# STM32.net
KiCad netlist of a schematic drawn in Altium Designer
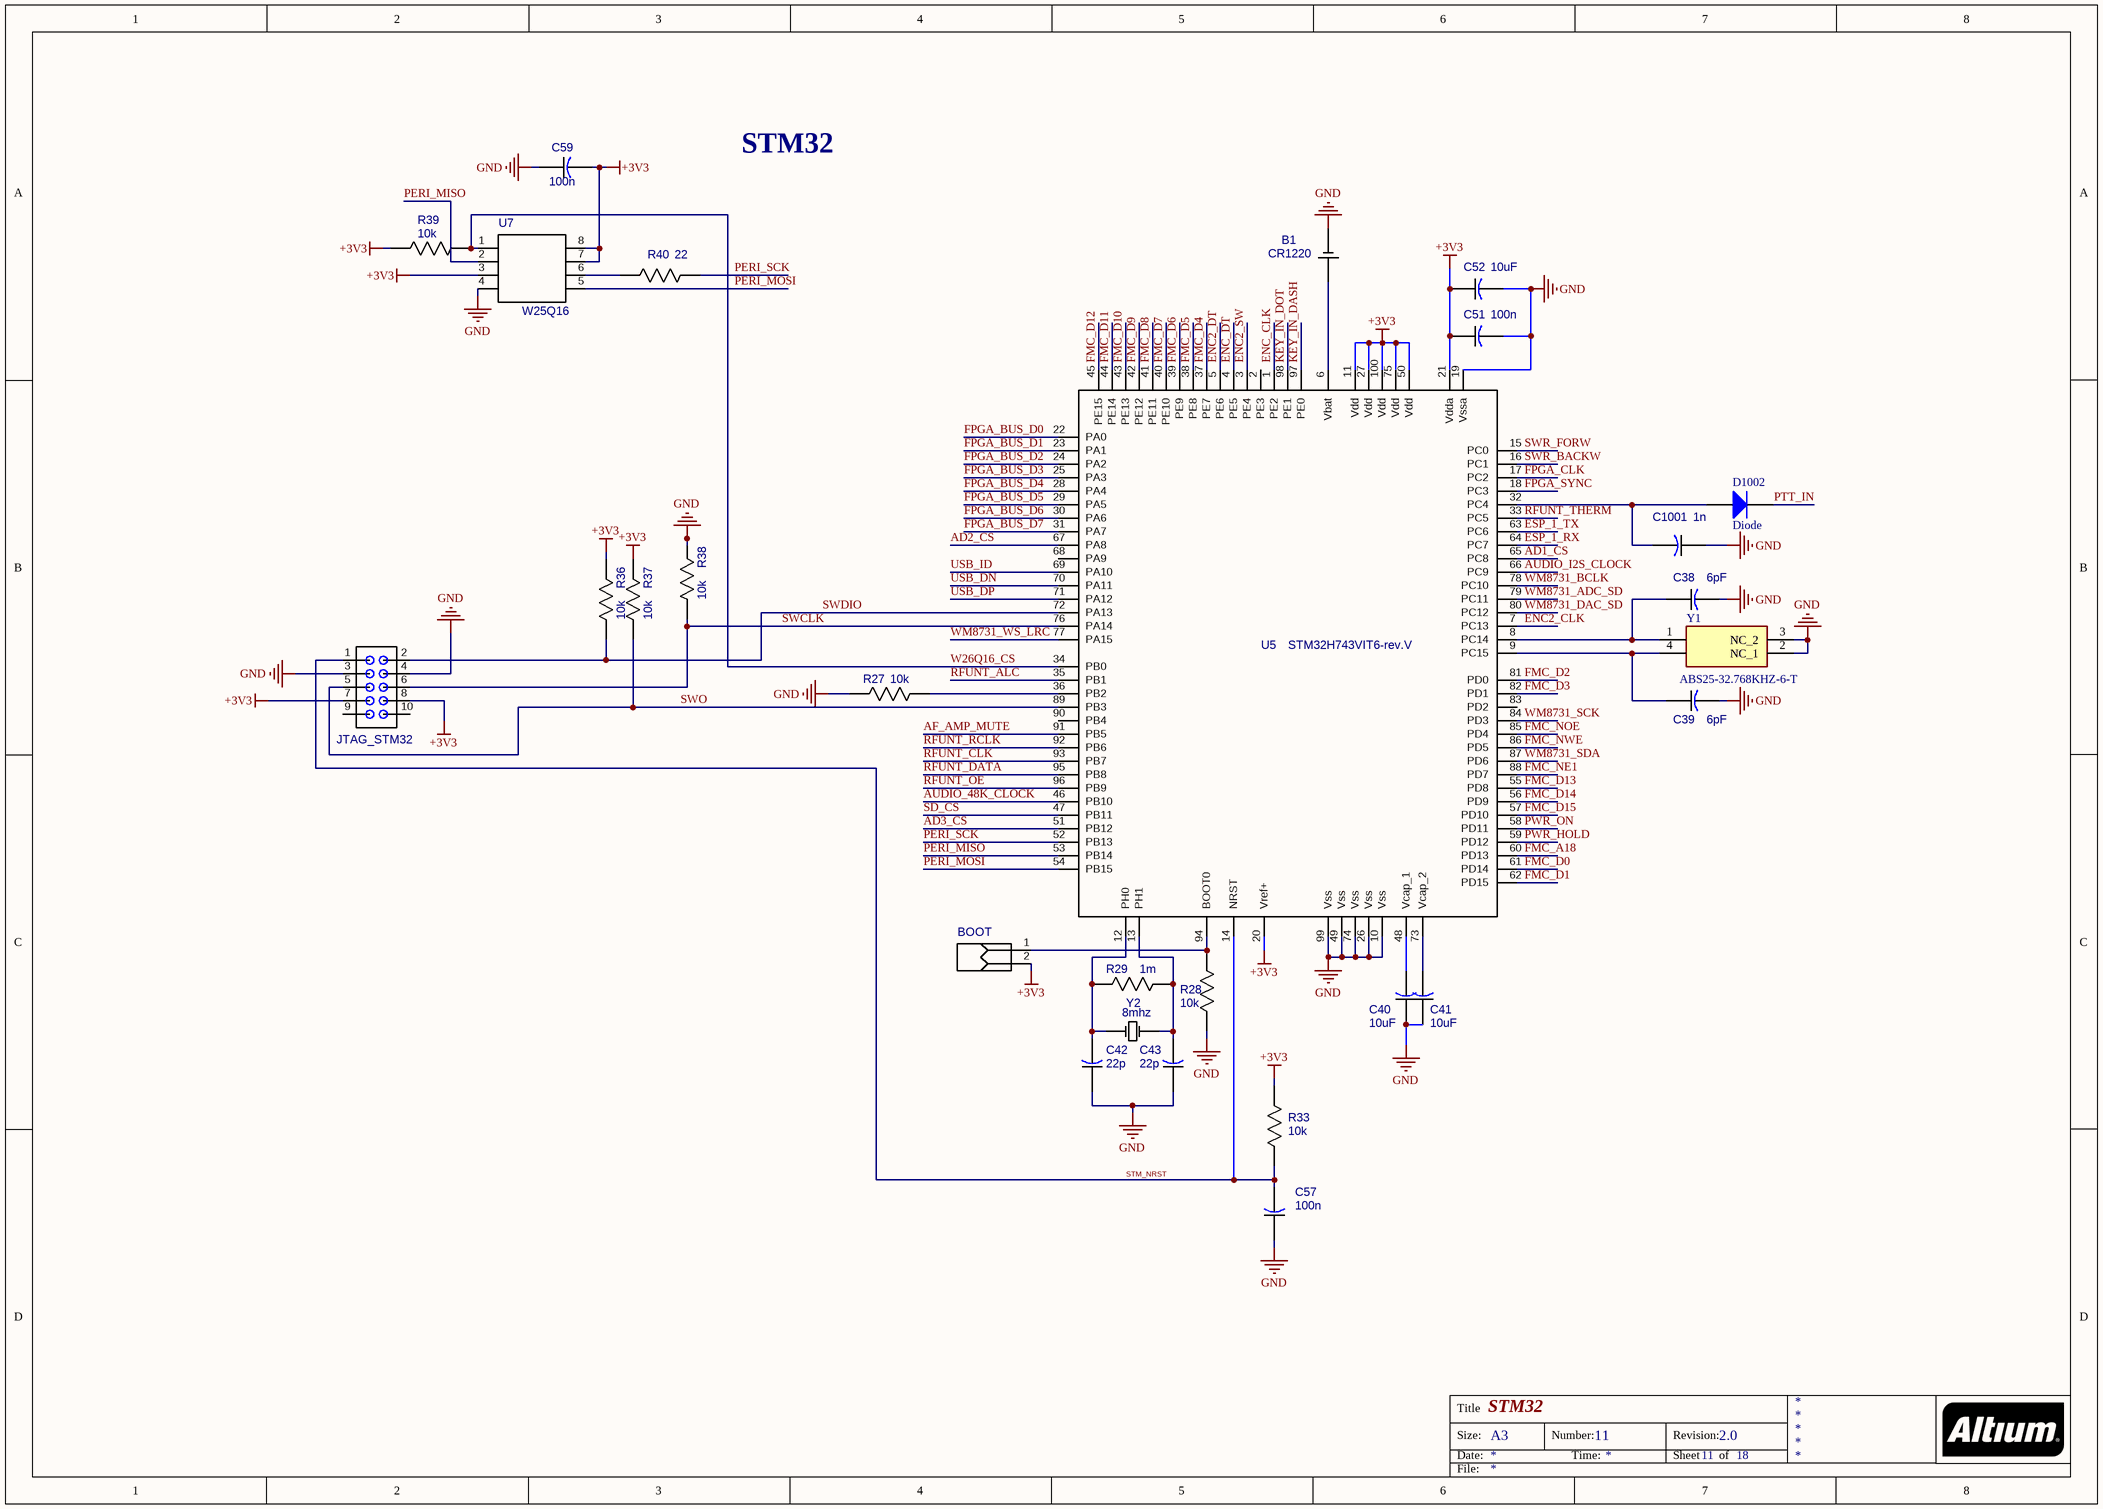
[diagram p0: STM32.SchDoc]

(export (version "E")
  (design (tool "Eeschema 10.0.6"))
  (components
    (comp (ref "B1")
      (value "CR1220")
      (footprint "KLS5-CR1220-01")
      (description "BR1632A/FA")
      (fields (field (name "Comment") "CR1220 +"))
      (libsource (lib "*") (part "BR1632A/FA"))
    )
    (comp (ref "BOOT")
      (value "~")
      (footprint "51022-0200")
      (description "2 Pin")
      (libsource (lib "*") (part "51022-0200"))
    )
    (comp (ref "C38")
      (value "6pF")
      (footprint "CAP_0805")
      (description "CAP_0805")
      (libsource (lib "*") (part "CAP_0805"))
    )
    (comp (ref "C39")
      (value "6pF")
      (footprint "CAP_0805")
      (description "CAP_0805")
      (libsource (lib "*") (part "CAP_0805"))
    )
    (comp (ref "C40")
      (value "10uF")
      (footprint "CAP_0805")
      (description "CAP_0805")
      (libsource (lib "*") (part "CAP_0805"))
    )
    (comp (ref "C41")
      (value "10uF")
      (footprint "CAP_0805")
      (description "CAP_0805")
      (libsource (lib "*") (part "CAP_0805"))
    )
    (comp (ref "C42")
      (value "22p")
      (footprint "CAP_0805")
      (description "CAP_0805")
      (libsource (lib "*") (part "CAP_0805"))
    )
    (comp (ref "C43")
      (value "22p")
      (footprint "CAP_0805")
      (description "CAP_0805")
      (libsource (lib "*") (part "CAP_0805"))
    )
    (comp (ref "C51")
      (value "100n")
      (footprint "CAP_0805")
      (description "CAP_0805")
      (libsource (lib "*") (part "CAP_0805"))
    )
    (comp (ref "C52")
      (value "10uF")
      (footprint "CAP_0805")
      (description "CAP_0805")
      (libsource (lib "*") (part "CAP_0805"))
    )
    (comp (ref "C57")
      (value "100n")
      (footprint "CAP_0805")
      (description "CAP_0805")
      (libsource (lib "*") (part "CAP_0805"))
    )
    (comp (ref "C59")
      (value "100n")
      (footprint "CAP_0805")
      (description "CAP_0805")
      (libsource (lib "*") (part "CAP_0805"))
    )
    (comp (ref "C1001")
      (value "1n")
      (footprint "CAP_0805")
      (description "CAP_0805")
      (libsource (lib "*") (part "CAP_0805"))
    )
    (comp (ref "D1002")
      (value "Diode")
      (footprint "C1206")
      (description "Default Diode")
      (fields (field (name "PUBLISHER") "Altium Limited"))
      (libsource (lib "Miscellaneous Devices") (part "Diode"))
    )
    (comp (ref "JTAG_STM32")
      (value "~")
      (footprint "IDC10")
      (description "2*5 Pin")
      (libsource (lib "*") (part "IDC10"))
    )
    (comp (ref "R27")
      (value "10k")
      (footprint "RES_0805")
      (description "RES_0805")
      (libsource (lib "*") (part "RES_0805"))
    )
    (comp (ref "R28")
      (value "10k")
      (footprint "RES_0805")
      (description "RES_0805")
      (libsource (lib "*") (part "RES_0805"))
    )
    (comp (ref "R29")
      (value "1m")
      (footprint "RES_0805")
      (description "RES_0805")
      (libsource (lib "*") (part "RES_0805"))
    )
    (comp (ref "R33")
      (value "10k")
      (footprint "RES_0805")
      (description "RES_0805")
      (libsource (lib "*") (part "RES_0805"))
    )
    (comp (ref "R36")
      (value "10k")
      (footprint "RES_0805")
      (description "RES_0805")
      (libsource (lib "*") (part "RES_0805"))
    )
    (comp (ref "R37")
      (value "10k")
      (footprint "RES_0805")
      (description "RES_0805")
      (libsource (lib "*") (part "RES_0805"))
    )
    (comp (ref "R38")
      (value "10k")
      (footprint "RES_0805")
      (description "RES_0805")
      (libsource (lib "*") (part "RES_0805"))
    )
    (comp (ref "R39")
      (value "10k")
      (footprint "RES_0805")
      (description "RES_0805")
      (libsource (lib "*") (part "RES_0805"))
    )
    (comp (ref "R40")
      (value "22")
      (footprint "RES_0805")
      (description "RES_0805")
      (libsource (lib "*") (part "RES_0805"))
    )
    (comp (ref "U5")
      (value "STM32H743VIT6-rev.V")
      (footprint "STM32H743VIT6")
      (description "STM32H743VIT6")
      (libsource (lib "*") (part "STM32H743VIT6"))
    )
    (comp (ref "U7") (value "W25Q16") (footprint "W25Q16") (libsource (lib "*") (part "W25Q16")))
    (comp (ref "Y1")
      (value "ABS25-32.768KHZ-6-T")
      (footprint "SamacSys:ABS25")
      (description "Crystal or Oscillator")
      (fields
        (field (name "MOUSER PART NUMBER") "815-ABS25-32.768K6-T")
        (field (name "RS PART NUMBER") "1712795P")
      )
      (libsource (lib "*") (part "ABS25-32.768KHZ-6-T"))
    )
    (comp (ref "Y2")
      (value "8mhz")
      (footprint "ECS-200-20-1")
      (description "ECS-200-20-1")
      (libsource (lib "*") (part "ECS-200-20-1"))
    )
  )
  (nets
    (net (code "1") (name "+3V3") (class "Default")
      (node (ref "BOOT") (pin "2") (pinfunction "2_2") (pintype "passive"))
      (node (ref "C51") (pin "1") (pinfunction "1_1") (pintype "passive"))
      (node (ref "C52") (pin "1") (pinfunction "1_1") (pintype "passive"))
      (node (ref "C59") (pin "2") (pinfunction "2_2") (pintype "passive"))
      (node (ref "JTAG_STM32") (pin "7") (pinfunction "7_7") (pintype "passive"))
      (node (ref "JTAG_STM32") (pin "8") (pinfunction "8_8") (pintype "passive"))
      (node (ref "R33") (pin "2") (pinfunction "2_2") (pintype "passive"))
      (node (ref "R36") (pin "1") (pinfunction "1_1") (pintype "passive"))
      (node (ref "R37") (pin "1") (pinfunction "1_1") (pintype "passive"))
      (node (ref "R39") (pin "1") (pinfunction "1_1") (pintype "passive"))
      (node (ref "U5") (pin "100") (pinfunction "Vdd_100") (pintype "passive"))
      (node (ref "U5") (pin "11") (pinfunction "Vdd_11") (pintype "passive"))
      (node (ref "U5") (pin "20") (pinfunction "Vref+_20") (pintype "passive"))
      (node (ref "U5") (pin "21") (pinfunction "Vdda_21") (pintype "passive"))
      (node (ref "U5") (pin "27") (pinfunction "Vdd_27") (pintype "passive"))
      (node (ref "U5") (pin "50") (pinfunction "Vdd_50") (pintype "passive"))
      (node (ref "U5") (pin "75") (pinfunction "Vdd_75") (pintype "passive"))
      (node (ref "U7") (pin "3") (pinfunction "WP_3") (pintype "passive"))
      (node (ref "U7") (pin "7") (pinfunction "HOLD_7") (pintype "passive"))
      (node (ref "U7") (pin "8") (pinfunction "VCC_8") (pintype "passive"))
    )
    (net (code "2") (name "/AD1_CS") (class "Default")
      (node (ref "U5") (pin "65") (pinfunction "PC8_65") (pintype "passive"))
    )
    (net (code "3") (name "/AD2_CS") (class "Default")
      (node (ref "U5") (pin "67") (pinfunction "PA8_67") (pintype "passive"))
    )
    (net (code "4") (name "/AD3_CS") (class "Default")
      (node (ref "U5") (pin "51") (pinfunction "PB12_51") (pintype "passive"))
    )
    (net (code "5") (name "/AF_AMP_MUTE") (class "Default")
      (node (ref "U5") (pin "91") (pinfunction "PB5_91") (pintype "passive"))
    )
    (net (code "6") (name "/AUDIO_48K_CLOCK") (class "Default")
      (node (ref "U5") (pin "46") (pinfunction "PB10_46") (pintype "passive"))
    )
    (net (code "7") (name "/AUDIO_I2S_CLOCK") (class "Default")
      (node (ref "U5") (pin "66") (pinfunction "PC9_66") (pintype "passive"))
    )
    (net (code "8") (name "/ENC2_CLK") (class "Default")
      (node (ref "U5") (pin "7") (pinfunction "PC13_7") (pintype "passive"))
    )
    (net (code "9") (name "/ENC2_DT") (class "Default")
      (node (ref "U5") (pin "5") (pinfunction "PE6_5") (pintype "passive"))
    )
    (net (code "10") (name "/ENC2_SW") (class "Default")
      (node (ref "U5") (pin "3") (pinfunction "PE4_3") (pintype "passive"))
    )
    (net (code "11") (name "/ENC_CLK") (class "Default")
      (node (ref "U5") (pin "1") (pinfunction "PE2_1") (pintype "passive"))
    )
    (net (code "12") (name "/ENC_DT") (class "Default")
      (node (ref "U5") (pin "4") (pinfunction "PE5_4") (pintype "passive"))
    )
    (net (code "13") (name "/ESP_1_RX") (class "Default")
      (node (ref "U5") (pin "64") (pinfunction "PC7_64") (pintype "passive"))
    )
    (net (code "14") (name "/ESP_1_TX") (class "Default")
      (node (ref "U5") (pin "63") (pinfunction "PC6_63") (pintype "passive"))
    )
    (net (code "15") (name "/FMC_A18") (class "Default")
      (node (ref "U5") (pin "60") (pinfunction "PD13_60") (pintype "passive"))
    )
    (net (code "16") (name "/FMC_D0") (class "Default")
      (node (ref "U5") (pin "61") (pinfunction "PD14_61") (pintype "passive"))
    )
    (net (code "17") (name "/FMC_D1") (class "Default")
      (node (ref "U5") (pin "62") (pinfunction "PD15_62") (pintype "passive"))
    )
    (net (code "18") (name "/FMC_D2") (class "Default")
      (node (ref "U5") (pin "81") (pinfunction "PD0_81") (pintype "passive"))
    )
    (net (code "19") (name "/FMC_D3") (class "Default")
      (node (ref "U5") (pin "82") (pinfunction "PD1_82") (pintype "passive"))
    )
    (net (code "20") (name "/FMC_D4") (class "Default")
      (node (ref "U5") (pin "37") (pinfunction "PE7_37") (pintype "passive"))
    )
    (net (code "21") (name "/FMC_D5") (class "Default")
      (node (ref "U5") (pin "38") (pinfunction "PE8_38") (pintype "passive"))
    )
    (net (code "22") (name "/FMC_D6") (class "Default")
      (node (ref "U5") (pin "39") (pinfunction "PE9_39") (pintype "passive"))
    )
    (net (code "23") (name "/FMC_D7") (class "Default")
      (node (ref "U5") (pin "40") (pinfunction "PE10_40") (pintype "passive"))
    )
    (net (code "24") (name "/FMC_D8") (class "Default")
      (node (ref "U5") (pin "41") (pinfunction "PE11_41") (pintype "passive"))
    )
    (net (code "25") (name "/FMC_D9") (class "Default")
      (node (ref "U5") (pin "42") (pinfunction "PE12_42") (pintype "passive"))
    )
    (net (code "26") (name "/FMC_D10") (class "Default")
      (node (ref "U5") (pin "43") (pinfunction "PE13_43") (pintype "passive"))
    )
    (net (code "27") (name "/FMC_D11") (class "Default")
      (node (ref "U5") (pin "44") (pinfunction "PE14_44") (pintype "passive"))
    )
    (net (code "28") (name "/FMC_D12") (class "Default")
      (node (ref "U5") (pin "45") (pinfunction "PE15_45") (pintype "passive"))
    )
    (net (code "29") (name "/FMC_D13") (class "Default")
      (node (ref "U5") (pin "55") (pinfunction "PD8_55") (pintype "passive"))
    )
    (net (code "30") (name "/FMC_D14") (class "Default")
      (node (ref "U5") (pin "56") (pinfunction "PD9_56") (pintype "passive"))
    )
    (net (code "31") (name "/FMC_D15") (class "Default")
      (node (ref "U5") (pin "57") (pinfunction "PD10_57") (pintype "passive"))
    )
    (net (code "32") (name "/FMC_NE1") (class "Default")
      (node (ref "U5") (pin "88") (pinfunction "PD7_88") (pintype "passive"))
    )
    (net (code "33") (name "/FMC_NOE") (class "Default")
      (node (ref "U5") (pin "85") (pinfunction "PD4_85") (pintype "passive"))
    )
    (net (code "34") (name "/FMC_NWE") (class "Default")
      (node (ref "U5") (pin "86") (pinfunction "PD5_86") (pintype "passive"))
    )
    (net (code "35") (name "/FPGA_BUS_D0") (class "Default")
      (node (ref "U5") (pin "22") (pinfunction "PA0_22") (pintype "passive"))
    )
    (net (code "36") (name "/FPGA_BUS_D1") (class "Default")
      (node (ref "U5") (pin "23") (pinfunction "PA1_23") (pintype "passive"))
    )
    (net (code "37") (name "/FPGA_BUS_D2") (class "Default")
      (node (ref "U5") (pin "24") (pinfunction "PA2_24") (pintype "passive"))
    )
    (net (code "38") (name "/FPGA_BUS_D3") (class "Default")
      (node (ref "U5") (pin "25") (pinfunction "PA3_25") (pintype "passive"))
    )
    (net (code "39") (name "/FPGA_BUS_D4") (class "Default")
      (node (ref "U5") (pin "28") (pinfunction "PA4_28") (pintype "passive"))
    )
    (net (code "40") (name "/FPGA_BUS_D5") (class "Default")
      (node (ref "U5") (pin "29") (pinfunction "PA5_29") (pintype "passive"))
    )
    (net (code "41") (name "/FPGA_BUS_D6") (class "Default")
      (node (ref "U5") (pin "30") (pinfunction "PA6_30") (pintype "passive"))
    )
    (net (code "42") (name "/FPGA_BUS_D7") (class "Default")
      (node (ref "U5") (pin "31") (pinfunction "PA7_31") (pintype "passive"))
    )
    (net (code "43") (name "/FPGA_CLK") (class "Default")
      (node (ref "U5") (pin "17") (pinfunction "PC2_17") (pintype "passive"))
    )
    (net (code "44") (name "/FPGA_SYNC") (class "Default")
      (node (ref "U5") (pin "18") (pinfunction "PC3_18") (pintype "passive"))
    )
    (net (code "45") (name "/KEY_IN_DASH") (class "Default")
      (node (ref "U5") (pin "97") (pinfunction "PE0_97") (pintype "passive"))
    )
    (net (code "46") (name "/KEY_IN_DOT") (class "Default")
      (node (ref "U5") (pin "98") (pinfunction "PE1_98") (pintype "passive"))
    )
    (net (code "47") (name "/PERI_MISO") (class "Default")
      (node (ref "U5") (pin "53") (pinfunction "PB14_53") (pintype "passive"))
      (node (ref "U7") (pin "2") (pinfunction "SO_2") (pintype "passive"))
    )
    (net (code "48") (name "/PERI_MOSI") (class "Default")
      (node (ref "U5") (pin "54") (pinfunction "PB15_54") (pintype "passive"))
      (node (ref "U7") (pin "5") (pinfunction "SI_5") (pintype "passive"))
    )
    (net (code "49") (name "/PERI_SCK") (class "Default")
      (node (ref "R40") (pin "2") (pinfunction "2_2") (pintype "passive"))
      (node (ref "U5") (pin "52") (pinfunction "PB13_52") (pintype "passive"))
    )
    (net (code "50") (name "/PTT_IN") (class "Default")
      (node (ref "D1002") (pin "2") (pinfunction "K_2") (pintype "passive"))
    )
    (net (code "51") (name "/PWR_HOLD") (class "Default")
      (node (ref "U5") (pin "59") (pinfunction "PD12_59") (pintype "passive"))
    )
    (net (code "52") (name "/PWR_ON") (class "Default")
      (node (ref "U5") (pin "58") (pinfunction "PD11_58") (pintype "passive"))
    )
    (net (code "53") (name "/RFUNT_ALC") (class "Default")
      (node (ref "U5") (pin "35") (pinfunction "PB1_35") (pintype "passive"))
    )
    (net (code "54") (name "/RFUNT_CLK") (class "Default")
      (node (ref "U5") (pin "93") (pinfunction "PB7_93") (pintype "passive"))
    )
    (net (code "55") (name "/RFUNT_DATA") (class "Default")
      (node (ref "U5") (pin "95") (pinfunction "PB8_95") (pintype "passive"))
    )
    (net (code "56") (name "/RFUNT_OE") (class "Default")
      (node (ref "U5") (pin "96") (pinfunction "PB9_96") (pintype "passive"))
    )
    (net (code "57") (name "/RFUNT_RCLK") (class "Default")
      (node (ref "U5") (pin "92") (pinfunction "PB6_92") (pintype "passive"))
    )
    (net (code "58") (name "/RFUNT_THERM") (class "Default")
      (node (ref "U5") (pin "33") (pinfunction "PC5_33") (pintype "passive"))
    )
    (net (code "59") (name "/SD_CS") (class "Default")
      (node (ref "U5") (pin "47") (pinfunction "PB11_47") (pintype "passive"))
    )
    (net (code "60") (name "/STM_NRST") (class "Default")
      (node (ref "C57") (pin "2") (pinfunction "2_2") (pintype "passive"))
      (node (ref "JTAG_STM32") (pin "1") (pinfunction "1_1") (pintype "passive"))
      (node (ref "R33") (pin "1") (pinfunction "1_1") (pintype "passive"))
      (node (ref "U5") (pin "14") (pinfunction "NRST_14") (pintype "passive"))
    )
    (net (code "61") (name "/SWCLK") (class "Default")
      (node (ref "JTAG_STM32") (pin "6") (pinfunction "6_6") (pintype "passive"))
      (node (ref "R38") (pin "2") (pinfunction "2_2") (pintype "passive"))
      (node (ref "U5") (pin "76") (pinfunction "PA14_76") (pintype "passive"))
    )
    (net (code "62") (name "/SWDIO") (class "Default")
      (node (ref "JTAG_STM32") (pin "2") (pinfunction "2_2") (pintype "passive"))
      (node (ref "R36") (pin "2") (pinfunction "2_2") (pintype "passive"))
      (node (ref "U5") (pin "72") (pinfunction "PA13_72") (pintype "passive"))
    )
    (net (code "63") (name "/SWO") (class "Default")
      (node (ref "JTAG_STM32") (pin "5") (pinfunction "5_5") (pintype "passive"))
      (node (ref "R37") (pin "2") (pinfunction "2_2") (pintype "passive"))
      (node (ref "U5") (pin "89") (pinfunction "PB3_89") (pintype "passive"))
    )
    (net (code "64") (name "/SWR_BACKW") (class "Default")
      (node (ref "U5") (pin "16") (pinfunction "PC1_16") (pintype "passive"))
    )
    (net (code "65") (name "/SWR_FORW") (class "Default")
      (node (ref "U5") (pin "15") (pinfunction "PC0_15") (pintype "passive"))
    )
    (net (code "66") (name "/USB_DN") (class "Default")
      (node (ref "U5") (pin "70") (pinfunction "PA11_70") (pintype "passive"))
    )
    (net (code "67") (name "/USB_DP") (class "Default")
      (node (ref "U5") (pin "71") (pinfunction "PA12_71") (pintype "passive"))
    )
    (net (code "68") (name "/USB_ID") (class "Default")
      (node (ref "U5") (pin "69") (pinfunction "PA10_69") (pintype "passive"))
    )
    (net (code "69") (name "/W26Q16_CS") (class "Default")
      (node (ref "R39") (pin "2") (pinfunction "2_2") (pintype "passive"))
      (node (ref "U5") (pin "34") (pinfunction "PB0_34") (pintype "passive"))
      (node (ref "U7") (pin "1") (pinfunction "CS_1") (pintype "passive"))
    )
    (net (code "70") (name "/WM8731_ADC_SD") (class "Default")
      (node (ref "U5") (pin "79") (pinfunction "PC11_79") (pintype "passive"))
    )
    (net (code "71") (name "/WM8731_BCLK") (class "Default")
      (node (ref "U5") (pin "78") (pinfunction "PC10_78") (pintype "passive"))
    )
    (net (code "72") (name "/WM8731_DAC_SD") (class "Default")
      (node (ref "U5") (pin "80") (pinfunction "PC12_80") (pintype "passive"))
    )
    (net (code "73") (name "/WM8731_SCK") (class "Default")
      (node (ref "U5") (pin "84") (pinfunction "PD3_84") (pintype "passive"))
    )
    (net (code "74") (name "/WM8731_SDA") (class "Default")
      (node (ref "U5") (pin "87") (pinfunction "PD6_87") (pintype "passive"))
    )
    (net (code "75") (name "/WM8731_WS_LRC") (class "Default")
      (node (ref "U5") (pin "77") (pinfunction "PA15_77") (pintype "passive"))
    )
    (net (code "76") (name "GND") (class "Default")
      (node (ref "B1") (pin "2") (pinfunction "NEG_2") (pintype "passive"))
      (node (ref "C1001") (pin "1") (pinfunction "1_1") (pintype "passive"))
      (node (ref "C38") (pin "2") (pinfunction "2_2") (pintype "passive"))
      (node (ref "C39") (pin "2") (pinfunction "2_2") (pintype "passive"))
      (node (ref "C40") (pin "1") (pinfunction "1_1") (pintype "passive"))
      (node (ref "C41") (pin "1") (pinfunction "1_1") (pintype "passive"))
      (node (ref "C42") (pin "1") (pinfunction "1_1") (pintype "passive"))
      (node (ref "C43") (pin "1") (pinfunction "1_1") (pintype "passive"))
      (node (ref "C51") (pin "2") (pinfunction "2_2") (pintype "passive"))
      (node (ref "C52") (pin "2") (pinfunction "2_2") (pintype "passive"))
      (node (ref "C57") (pin "1") (pinfunction "1_1") (pintype "passive"))
      (node (ref "C59") (pin "1") (pinfunction "1_1") (pintype "passive"))
      (node (ref "JTAG_STM32") (pin "3") (pinfunction "3_3") (pintype "passive"))
      (node (ref "JTAG_STM32") (pin "4") (pinfunction "4_4") (pintype "passive"))
      (node (ref "R27") (pin "1") (pinfunction "1_1") (pintype "passive"))
      (node (ref "R28") (pin "1") (pinfunction "1_1") (pintype "passive"))
      (node (ref "R38") (pin "1") (pinfunction "1_1") (pintype "passive"))
      (node (ref "U5") (pin "10") (pinfunction "Vss_10") (pintype "passive"))
      (node (ref "U5") (pin "19") (pinfunction "Vssa_19") (pintype "passive"))
      (node (ref "U5") (pin "26") (pinfunction "Vss_26") (pintype "passive"))
      (node (ref "U5") (pin "49") (pinfunction "Vss_49") (pintype "passive"))
      (node (ref "U5") (pin "74") (pinfunction "Vss_74") (pintype "passive"))
      (node (ref "U5") (pin "99") (pinfunction "Vss_99") (pintype "passive"))
      (node (ref "U7") (pin "4") (pinfunction "GND_4") (pintype "passive"))
      (node (ref "Y1") (pin "2") (pinfunction "NC_1_2") (pintype "passive"))
      (node (ref "Y1") (pin "3") (pinfunction "NC_2_3") (pintype "passive"))
    )
    (net (code "77") (name "Net-(B1-POS)") (class "Default")
      (node (ref "B1") (pin "1") (pinfunction "POS_1") (pintype "passive"))
      (node (ref "U5") (pin "6") (pinfunction "Vbat_6") (pintype "passive"))
    )
    (net (code "78") (name "Net-(D1002-A)") (class "Default")
      (node (ref "C1001") (pin "2") (pinfunction "2_2") (pintype "passive"))
      (node (ref "D1002") (pin "1") (pinfunction "A_1") (pintype "passive"))
      (node (ref "U5") (pin "32") (pinfunction "PC4_32") (pintype "passive"))
    )
    (net (code "79") (name "Net-(U5-BOOT0)") (class "Default")
      (node (ref "BOOT") (pin "1") (pinfunction "1_1") (pintype "passive"))
      (node (ref "R28") (pin "2") (pinfunction "2_2") (pintype "passive"))
      (node (ref "U5") (pin "94") (pinfunction "BOOT0_94") (pintype "passive"))
    )
    (net (code "80") (name "Net-(U5-PB2)") (class "Default")
      (node (ref "R27") (pin "2") (pinfunction "2_2") (pintype "passive"))
      (node (ref "U5") (pin "36") (pinfunction "PB2_36") (pintype "passive"))
    )
    (net (code "81") (name "Net-(U5-PC14)") (class "Default")
      (node (ref "C38") (pin "1") (pinfunction "1_1") (pintype "passive"))
      (node (ref "U5") (pin "8") (pinfunction "PC14_8") (pintype "passive"))
      (node (ref "Y1") (pin "1") (pinfunction "1_1") (pintype "passive"))
    )
    (net (code "82") (name "Net-(U5-PC15)") (class "Default")
      (node (ref "C39") (pin "1") (pinfunction "1_1") (pintype "passive"))
      (node (ref "U5") (pin "9") (pinfunction "PC15_9") (pintype "passive"))
      (node (ref "Y1") (pin "4") (pinfunction "4_4") (pintype "passive"))
    )
    (net (code "83") (name "Net-(U5-PH0)") (class "Default")
      (node (ref "C42") (pin "2") (pinfunction "2_2") (pintype "passive"))
      (node (ref "R29") (pin "1") (pinfunction "1_1") (pintype "passive"))
      (node (ref "U5") (pin "12") (pinfunction "PH0_12") (pintype "passive"))
      (node (ref "Y2") (pin "1") (pinfunction "OSC1_1") (pintype "passive"))
    )
    (net (code "84") (name "Net-(U5-PH1)") (class "Default")
      (node (ref "C43") (pin "2") (pinfunction "2_2") (pintype "passive"))
      (node (ref "R29") (pin "2") (pinfunction "2_2") (pintype "passive"))
      (node (ref "U5") (pin "13") (pinfunction "PH1_13") (pintype "passive"))
      (node (ref "Y2") (pin "2") (pinfunction "OSC2_2") (pintype "passive"))
    )
    (net (code "85") (name "Net-(U5-Vcap_1)") (class "Default")
      (node (ref "C40") (pin "2") (pinfunction "2_2") (pintype "passive"))
      (node (ref "U5") (pin "48") (pinfunction "Vcap_1_48") (pintype "passive"))
    )
    (net (code "86") (name "Net-(U5-Vcap_2)") (class "Default")
      (node (ref "C41") (pin "2") (pinfunction "2_2") (pintype "passive"))
      (node (ref "U5") (pin "73") (pinfunction "Vcap_2_73") (pintype "passive"))
    )
    (net (code "87") (name "Net-(U7-CLK)") (class "Default")
      (node (ref "R40") (pin "1") (pinfunction "1_1") (pintype "passive"))
      (node (ref "U7") (pin "6") (pinfunction "CLK_6") (pintype "passive"))
    )
    (net (code "88") (name "unconnected-(JTAG_STM32-Pad9)") (class "Default")
      (node (ref "JTAG_STM32") (pin "9") (pinfunction "9_9") (pintype "passive"))
    )
    (net (code "89") (name "unconnected-(JTAG_STM32-Pad10)") (class "Default")
      (node (ref "JTAG_STM32") (pin "10") (pinfunction "10_10") (pintype "passive"))
    )
    (net (code "90") (name "unconnected-(U5-PA9-Pad68)") (class "Default")
      (node (ref "U5") (pin "68") (pinfunction "PA9_68") (pintype "passive"))
    )
    (net (code "91") (name "unconnected-(U5-PB4-Pad90)") (class "Default")
      (node (ref "U5") (pin "90") (pinfunction "PB4_90") (pintype "passive"))
    )
    (net (code "92") (name "unconnected-(U5-PD2-Pad83)") (class "Default")
      (node (ref "U5") (pin "83") (pinfunction "PD2_83") (pintype "passive"))
    )
    (net (code "93") (name "unconnected-(U5-PE3-Pad2)") (class "Default")
      (node (ref "U5") (pin "2") (pinfunction "PE3_2") (pintype "passive"))
    )
  )
)
